# untitled.net
KiCad netlist of a schematic drawn in EAGLE
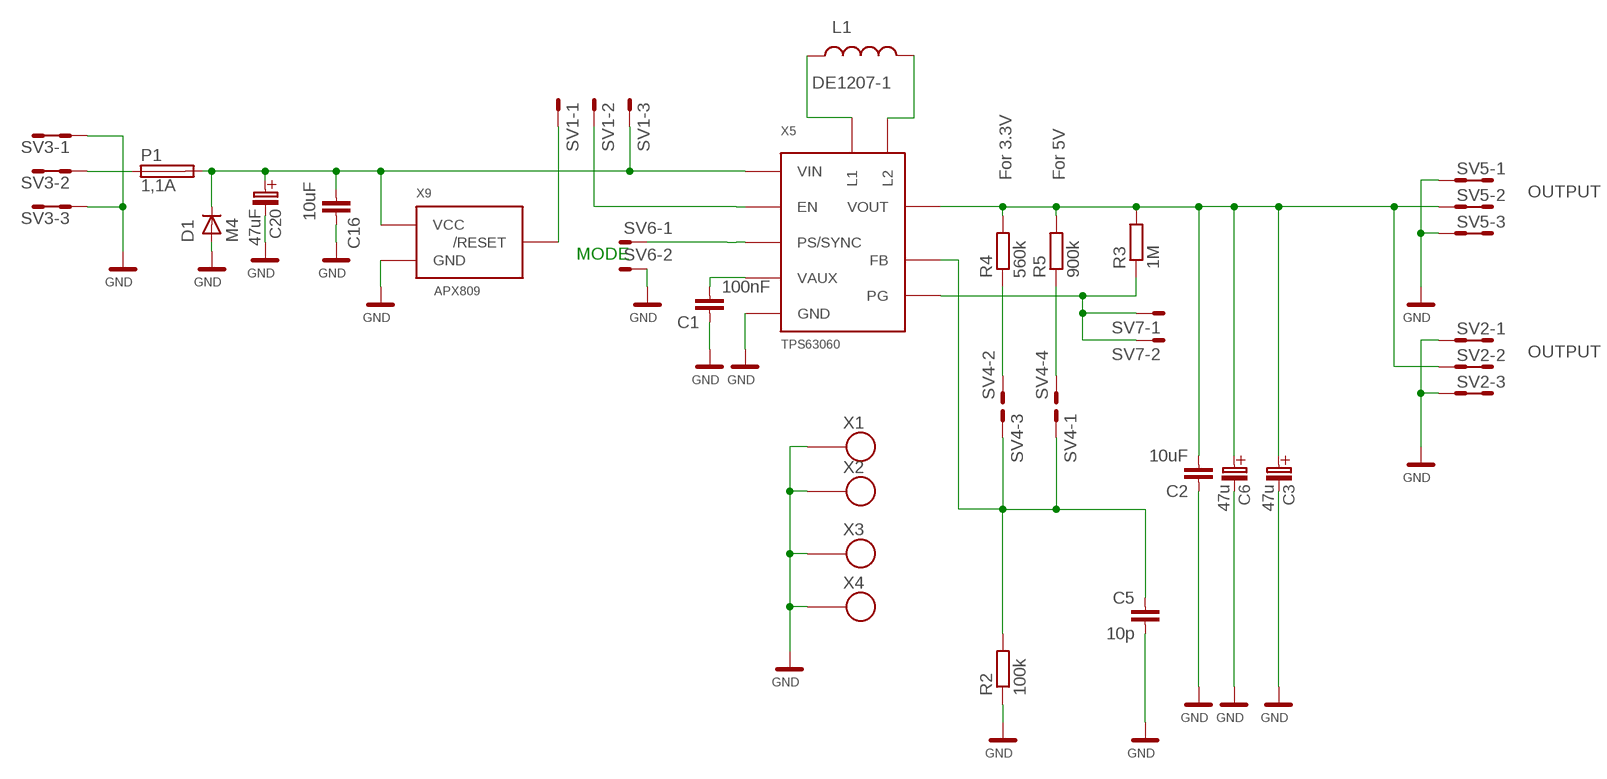
[diagram p0: schematic, sheet 1]

(export (version "E")
  (design (tool "Eeschema 10.0.6"))
  (components
    (comp (ref "C1")
      (value "100nF")
      (footprint "eagle-import:C0805")
      (libsource (lib "eagle-import") (part "C0805"))
    )
    (comp (ref "C2")
      (value "10uF")
      (footprint "eagle-import:C0805")
      (libsource (lib "eagle-import") (part "C0805"))
    )
    (comp (ref "C3") (value "47u") (footprint "eagle-import:C") (libsource (lib "eagle-import") (part "C")))
    (comp (ref "C5")
      (value "10p")
      (footprint "eagle-import:C0805")
      (libsource (lib "eagle-import") (part "C0805"))
    )
    (comp (ref "C6") (value "47u") (footprint "eagle-import:C") (libsource (lib "eagle-import") (part "C")))
    (comp (ref "C16")
      (value "10uF")
      (footprint "eagle-import:C0805")
      (libsource (lib "eagle-import") (part "C0805"))
    )
    (comp (ref "C20") (value "47uF") (footprint "eagle-import:C") (libsource (lib "eagle-import") (part "C")))
    (comp (ref "D1")
      (value "M4")
      (footprint "eagle-import:SMA")
      (libsource (lib "eagle-import") (part "D-OB.SMA"))
    )
    (comp (ref "L1")
      (value "DE1207-1")
      (footprint "eagle-import:DE1205-10")
      (libsource (lib "eagle-import") (part "DE1205-10"))
    )
    (comp (ref "P1")
      (value "1,1A")
      (footprint "eagle-import:1812")
      (libsource (lib "eagle-import") (part "POJISTKA_1812"))
    )
    (comp (ref "R2")
      (value "100k")
      (footprint "eagle-import:0805")
      (libsource (lib "eagle-import") (part "R0805"))
    )
    (comp (ref "R3")
      (value "1M")
      (footprint "eagle-import:0805")
      (libsource (lib "eagle-import") (part "R0805"))
    )
    (comp (ref "R4")
      (value "560k")
      (footprint "eagle-import:0805")
      (libsource (lib "eagle-import") (part "R0805"))
    )
    (comp (ref "R5")
      (value "900k")
      (footprint "eagle-import:0805")
      (libsource (lib "eagle-import") (part "R0805"))
    )
    (comp (ref "SV1")
      (value "MA03-1")
      (footprint "eagle-import:MA03-1")
      (libsource (lib "eagle-import") (part "MA03-1"))
    )
    (comp (ref "SV2")
      (value "MA03-2")
      (footprint "eagle-import:MA03-2")
      (libsource (lib "eagle-import") (part "MA03-2"))
    )
    (comp (ref "SV3")
      (value "MA03-2")
      (footprint "eagle-import:MA03-2")
      (libsource (lib "eagle-import") (part "MA03-2"))
    )
    (comp (ref "SV4")
      (value "MA02-3")
      (footprint "eagle-import:MA02-2")
      (libsource (lib "eagle-import") (part "MA02-3"))
    )
    (comp (ref "SV5")
      (value "MA03-2")
      (footprint "eagle-import:MA03-2")
      (libsource (lib "eagle-import") (part "MA03-2"))
    )
    (comp (ref "SV6")
      (value "MA02-1")
      (footprint "eagle-import:MA02-1")
      (libsource (lib "eagle-import") (part "MA02-1"))
    )
    (comp (ref "SV7")
      (value "MA02-1")
      (footprint "eagle-import:MA02-1")
      (libsource (lib "eagle-import") (part "MA02-1"))
    )
    (comp (ref "X1")
      (value "SROUB3M")
      (footprint "eagle-import:SROUB3M")
      (libsource (lib "eagle-import") (part "SROUB3M"))
    )
    (comp (ref "X2")
      (value "SROUB3M")
      (footprint "eagle-import:SROUB3M")
      (libsource (lib "eagle-import") (part "SROUB3M"))
    )
    (comp (ref "X3")
      (value "SROUB3M")
      (footprint "eagle-import:SROUB3M")
      (libsource (lib "eagle-import") (part "SROUB3M"))
    )
    (comp (ref "X4")
      (value "SROUB3M")
      (footprint "eagle-import:SROUB3M")
      (libsource (lib "eagle-import") (part "SROUB3M"))
    )
    (comp (ref "X5")
      (value "TPS63060")
      (footprint "eagle-import:SON10")
      (libsource (lib "eagle-import") (part "TPS63060"))
    )
    (comp (ref "X9")
      (value "APX809")
      (footprint "eagle-import:SOT23")
      (libsource (lib "eagle-import") (part "APX809-26SA"))
    )
  )
  (nets
    (net (code "1") (name "GND") (class "Default")
      (node (ref "C1") (pin "1") (pinfunction "1_1") (pintype "passive"))
      (node (ref "C16") (pin "1") (pinfunction "1_1") (pintype "passive"))
      (node (ref "C2") (pin "1") (pinfunction "1_1") (pintype "passive"))
      (node (ref "C20") (pin "-") (pinfunction "C_EL-_-") (pintype "passive"))
      (node (ref "C3") (pin "-") (pinfunction "C_EL-_-") (pintype "passive"))
      (node (ref "C5") (pin "2") (pinfunction "2_2") (pintype "passive"))
      (node (ref "C6") (pin "-") (pinfunction "C_EL-_-") (pintype "passive"))
      (node (ref "D1") (pin "A") (pinfunction "A_A") (pintype "passive"))
      (node (ref "R2") (pin "1") (pinfunction "1_1") (pintype "passive"))
      (node (ref "SV2") (pin "1") (pinfunction "K_1") (pintype "passive"))
      (node (ref "SV2") (pin "2") (pinfunction "K_2") (pintype "passive"))
      (node (ref "SV2") (pin "5") (pinfunction "K_5") (pintype "passive"))
      (node (ref "SV2") (pin "6") (pinfunction "K_6") (pintype "passive"))
      (node (ref "SV3") (pin "1") (pinfunction "K_1") (pintype "passive"))
      (node (ref "SV3") (pin "2") (pinfunction "K_2") (pintype "passive"))
      (node (ref "SV3") (pin "5") (pinfunction "K_5") (pintype "passive"))
      (node (ref "SV3") (pin "6") (pinfunction "K_6") (pintype "passive"))
      (node (ref "SV5") (pin "1") (pinfunction "K_1") (pintype "passive"))
      (node (ref "SV5") (pin "2") (pinfunction "K_2") (pintype "passive"))
      (node (ref "SV5") (pin "5") (pinfunction "K_5") (pintype "passive"))
      (node (ref "SV5") (pin "6") (pinfunction "K_6") (pintype "passive"))
      (node (ref "SV6") (pin "2") (pinfunction "P$1_2") (pintype "passive"))
      (node (ref "X1") (pin "P$1") (pinfunction "P$1_P$1") (pintype "bidirectional"))
      (node (ref "X2") (pin "P$1") (pinfunction "P$1_P$1") (pintype "bidirectional"))
      (node (ref "X3") (pin "P$1") (pinfunction "P$1_P$1") (pintype "bidirectional"))
      (node (ref "X4") (pin "P$1") (pinfunction "P$1_P$1") (pintype "bidirectional"))
      (node (ref "X5") (pin "11") (pinfunction "GND_11") (pintype "passive"))
      (node (ref "X5") (pin "12") (pinfunction "GND_12") (pintype "passive"))
      (node (ref "X5") (pin "13") (pinfunction "GND_13") (pintype "passive"))
      (node (ref "X5") (pin "14") (pinfunction "GND_14") (pintype "passive"))
      (node (ref "X5") (pin "15") (pinfunction "GND_15") (pintype "passive"))
      (node (ref "X5") (pin "16") (pinfunction "GND_16") (pintype "passive"))
      (node (ref "X5") (pin "17") (pinfunction "GND_17") (pintype "passive"))
      (node (ref "X5") (pin "18") (pinfunction "GND_18") (pintype "passive"))
      (node (ref "X5") (pin "19") (pinfunction "GND_19") (pintype "passive"))
      (node (ref "X5") (pin "21") (pinfunction "GND_21") (pintype "passive"))
      (node (ref "X5") (pin "7") (pinfunction "GND_7") (pintype "passive"))
      (node (ref "X5") (pin "P$1") (pinfunction "GND_P$1") (pintype "passive"))
      (node (ref "X5") (pin "P$2") (pinfunction "GND_P$2") (pintype "passive"))
      (node (ref "X5") (pin "P$3") (pinfunction "GND_P$3") (pintype "passive"))
      (node (ref "X5") (pin "P$4") (pinfunction "GND_P$4") (pintype "passive"))
      (node (ref "X5") (pin "P$5") (pinfunction "GND_P$5") (pintype "passive"))
      (node (ref "X9") (pin "1") (pinfunction "GND_1") (pintype "passive"))
    )
    (net (code "2") (name "Net-(C3-C_EL+)") (class "Default")
      (node (ref "C2") (pin "2") (pinfunction "2_2") (pintype "passive"))
      (node (ref "C3") (pin "+") (pinfunction "C_EL+_+") (pintype "passive"))
      (node (ref "C6") (pin "+") (pinfunction "C_EL+_+") (pintype "passive"))
      (node (ref "R3") (pin "2") (pinfunction "2_2") (pintype "passive"))
      (node (ref "R4") (pin "2") (pinfunction "2_2") (pintype "passive"))
      (node (ref "R5") (pin "2") (pinfunction "2_2") (pintype "passive"))
      (node (ref "SV2") (pin "3") (pinfunction "K_3") (pintype "passive"))
      (node (ref "SV2") (pin "4") (pinfunction "K_4") (pintype "passive"))
      (node (ref "SV5") (pin "3") (pinfunction "K_3") (pintype "passive"))
      (node (ref "SV5") (pin "4") (pinfunction "K_4") (pintype "passive"))
      (node (ref "X5") (pin "9") (pinfunction "VOUT_9") (pintype "output"))
    )
    (net (code "3") (name "Net-(C20-C_EL+)") (class "Default")
      (node (ref "C16") (pin "2") (pinfunction "2_2") (pintype "passive"))
      (node (ref "C20") (pin "+") (pinfunction "C_EL+_+") (pintype "passive"))
      (node (ref "D1") (pin "K") (pinfunction "C_K") (pintype "passive"))
      (node (ref "P1") (pin "2") (pinfunction "2_2") (pintype "passive"))
      (node (ref "SV1") (pin "3") (pinfunction "P$1_3") (pintype "passive"))
      (node (ref "X5") (pin "2") (pinfunction "VIN_2") (pintype "input"))
      (node (ref "X9") (pin "3") (pinfunction "VCC_3") (pintype "input"))
    )
    (net (code "4") (name "Net-(L1-1)") (class "Default")
      (node (ref "L1") (pin "P$1") (pinfunction "1_P$1") (pintype "passive"))
      (node (ref "X5") (pin "1") (pinfunction "L1_1") (pintype "passive"))
    )
    (net (code "5") (name "Net-(L1-2)") (class "Default")
      (node (ref "L1") (pin "P$2") (pinfunction "2_P$2") (pintype "passive"))
      (node (ref "X5") (pin "10") (pinfunction "L2_10") (pintype "passive"))
    )
    (net (code "6") (name "Net-(P1-Pad1)") (class "Default")
      (node (ref "P1") (pin "1") (pinfunction "1_1") (pintype "passive"))
      (node (ref "SV3") (pin "3") (pinfunction "K_3") (pintype "passive"))
      (node (ref "SV3") (pin "4") (pinfunction "K_4") (pintype "passive"))
    )
    (net (code "7") (name "Net-(SV1A-P$1)") (class "Default")
      (node (ref "SV1") (pin "1") (pinfunction "P$1_1") (pintype "passive"))
      (node (ref "X9") (pin "2") (pinfunction "/RESET_2") (pintype "passive"))
    )
    (net (code "8") (name "Net-(SV1B-P$1)") (class "Default")
      (node (ref "SV1") (pin "2") (pinfunction "P$1_2") (pintype "passive"))
      (node (ref "X5") (pin "3") (pinfunction "EN_3") (pintype "input"))
    )
    (net (code "9") (name "Net-(SV4A-P$1)") (class "Default")
      (node (ref "C5") (pin "1") (pinfunction "1_1") (pintype "passive"))
      (node (ref "R2") (pin "2") (pinfunction "2_2") (pintype "passive"))
      (node (ref "SV4") (pin "1") (pinfunction "P$1_1") (pintype "passive"))
      (node (ref "SV4") (pin "3") (pinfunction "P$1_3") (pintype "passive"))
      (node (ref "X5") (pin "8") (pinfunction "FB_8") (pintype "input"))
    )
    (net (code "10") (name "Net-(SV4B-P$1)") (class "Default")
      (node (ref "R4") (pin "1") (pinfunction "1_1") (pintype "passive"))
      (node (ref "SV4") (pin "2") (pinfunction "P$1_2") (pintype "passive"))
    )
    (net (code "11") (name "Net-(SV4D-P$1)") (class "Default")
      (node (ref "R5") (pin "1") (pinfunction "1_1") (pintype "passive"))
      (node (ref "SV4") (pin "4") (pinfunction "P$1_4") (pintype "passive"))
    )
    (net (code "12") (name "Net-(SV6A-P$1)") (class "Default")
      (node (ref "SV6") (pin "1") (pinfunction "P$1_1") (pintype "passive"))
      (node (ref "X5") (pin "4") (pinfunction "PS/SYNC_4") (pintype "input"))
    )
    (net (code "13") (name "Net-(SV7A-P$1)") (class "Default")
      (node (ref "R3") (pin "1") (pinfunction "1_1") (pintype "passive"))
      (node (ref "SV7") (pin "1") (pinfunction "P$1_1") (pintype "passive"))
      (node (ref "SV7") (pin "2") (pinfunction "P$1_2") (pintype "passive"))
      (node (ref "X5") (pin "5") (pinfunction "PG_5") (pintype "input"))
    )
    (net (code "14") (name "Net-(X5-VAUX)") (class "Default")
      (node (ref "C1") (pin "2") (pinfunction "2_2") (pintype "passive"))
      (node (ref "X5") (pin "6") (pinfunction "VAUX_6") (pintype "input"))
    )
  )
)
